# AMP_P2.net
KiCad netlist of a schematic drawn in Altium Designer
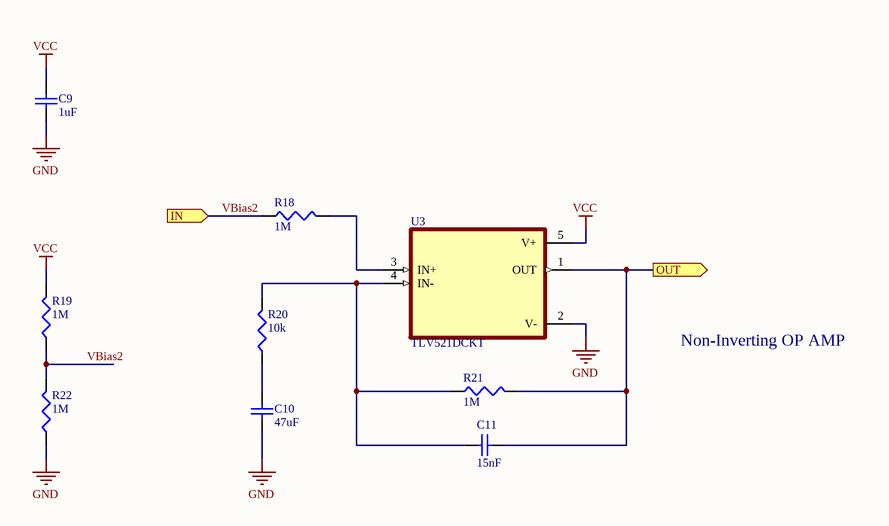
[diagram p0: AMP_P2.SchDoc]

(export (version "E")
  (design (tool "Eeschema 10.0.6"))
  (components
    (comp (ref "C9")
      (value "1uF")
      (footprint "SMD-0603")
      (description "Ceramic Capacitor 0603")
      (libsource (lib "LCR") (part "CAP0603"))
    )
    (comp (ref "C10")
      (value "47uF")
      (footprint "SMD-0603")
      (description "Ceramic Capacitor 0603")
      (libsource (lib "LCR") (part "CAP0603"))
    )
    (comp (ref "C11")
      (value "15nF")
      (footprint "SMD-0603")
      (description "Ceramic Capacitor 0603")
      (libsource (lib "LCR") (part "CAP0603"))
    )
    (comp (ref "R18")
      (value "1M")
      (footprint "SMD-0603")
      (description "Resistor-0603")
      (libsource (lib "LCR") (part "RES0603"))
    )
    (comp (ref "R19")
      (value "1M")
      (footprint "SMD-0603")
      (description "Resistor-0603")
      (libsource (lib "LCR") (part "RES0603"))
    )
    (comp (ref "R20")
      (value "10k")
      (footprint "SMD-0603")
      (description "Resistor-0603")
      (libsource (lib "LCR") (part "RES0603"))
    )
    (comp (ref "R21")
      (value "1M")
      (footprint "SMD-0603")
      (description "Resistor-0603")
      (libsource (lib "LCR") (part "RES0603"))
    )
    (comp (ref "R22")
      (value "1M")
      (footprint "SMD-0603")
      (description "Resistor-0603")
      (libsource (lib "LCR") (part "RES0603"))
    )
    (comp (ref "U3")
      (value "TLV521DCKT")
      (footprint "TLV521-SOT-5N")
      (fields (field (name "MF") "Texas Instruments"))
      (libsource (lib "op_amp") (part "TLV521DCKT"))
    )
  )
  (nets
    (net (code "1") (name "/OUT") (class "Default")
      (node (ref "C11") (pin "2") (pinfunction "2_2") (pintype "passive"))
      (node (ref "R21") (pin "2") (pinfunction "2_2") (pintype "passive"))
      (node (ref "U3") (pin "1") (pinfunction "OUT_1") (pintype "output"))
    )
    (net (code "2") (name "/VBias2") (class "Default")
      (node (ref "R18") (pin "1") (pinfunction "1_1") (pintype "passive"))
      (node (ref "R19") (pin "1") (pinfunction "1_1") (pintype "passive"))
      (node (ref "R22") (pin "2") (pinfunction "2_2") (pintype "passive"))
    )
    (net (code "3") (name "GND") (class "Default")
      (node (ref "C10") (pin "1") (pinfunction "1_1") (pintype "passive"))
      (node (ref "C9") (pin "1") (pinfunction "1_1") (pintype "passive"))
      (node (ref "R22") (pin "1") (pinfunction "1_1") (pintype "passive"))
      (node (ref "U3") (pin "2") (pinfunction "V-_2") (pintype "power_in"))
    )
    (net (code "4") (name "Net-(C10-Pad2)") (class "Default")
      (node (ref "C10") (pin "2") (pinfunction "2_2") (pintype "passive"))
      (node (ref "R20") (pin "1") (pinfunction "1_1") (pintype "passive"))
    )
    (net (code "5") (name "Net-(U3-IN+)") (class "Default")
      (node (ref "R18") (pin "2") (pinfunction "2_2") (pintype "passive"))
      (node (ref "U3") (pin "3") (pinfunction "IN+_3") (pintype "input"))
    )
    (net (code "6") (name "Net-(U3-IN-)") (class "Default")
      (node (ref "C11") (pin "1") (pinfunction "1_1") (pintype "passive"))
      (node (ref "R20") (pin "2") (pinfunction "2_2") (pintype "passive"))
      (node (ref "R21") (pin "1") (pinfunction "1_1") (pintype "passive"))
      (node (ref "U3") (pin "4") (pinfunction "IN-_4") (pintype "input"))
    )
    (net (code "7") (name "VCC") (class "Default")
      (node (ref "C9") (pin "2") (pinfunction "2_2") (pintype "passive"))
      (node (ref "R19") (pin "2") (pinfunction "2_2") (pintype "passive"))
      (node (ref "U3") (pin "5") (pinfunction "V+_5") (pintype "power_in"))
    )
  )
)
